# Input.net
KiCad netlist of a schematic drawn in Altium Designer
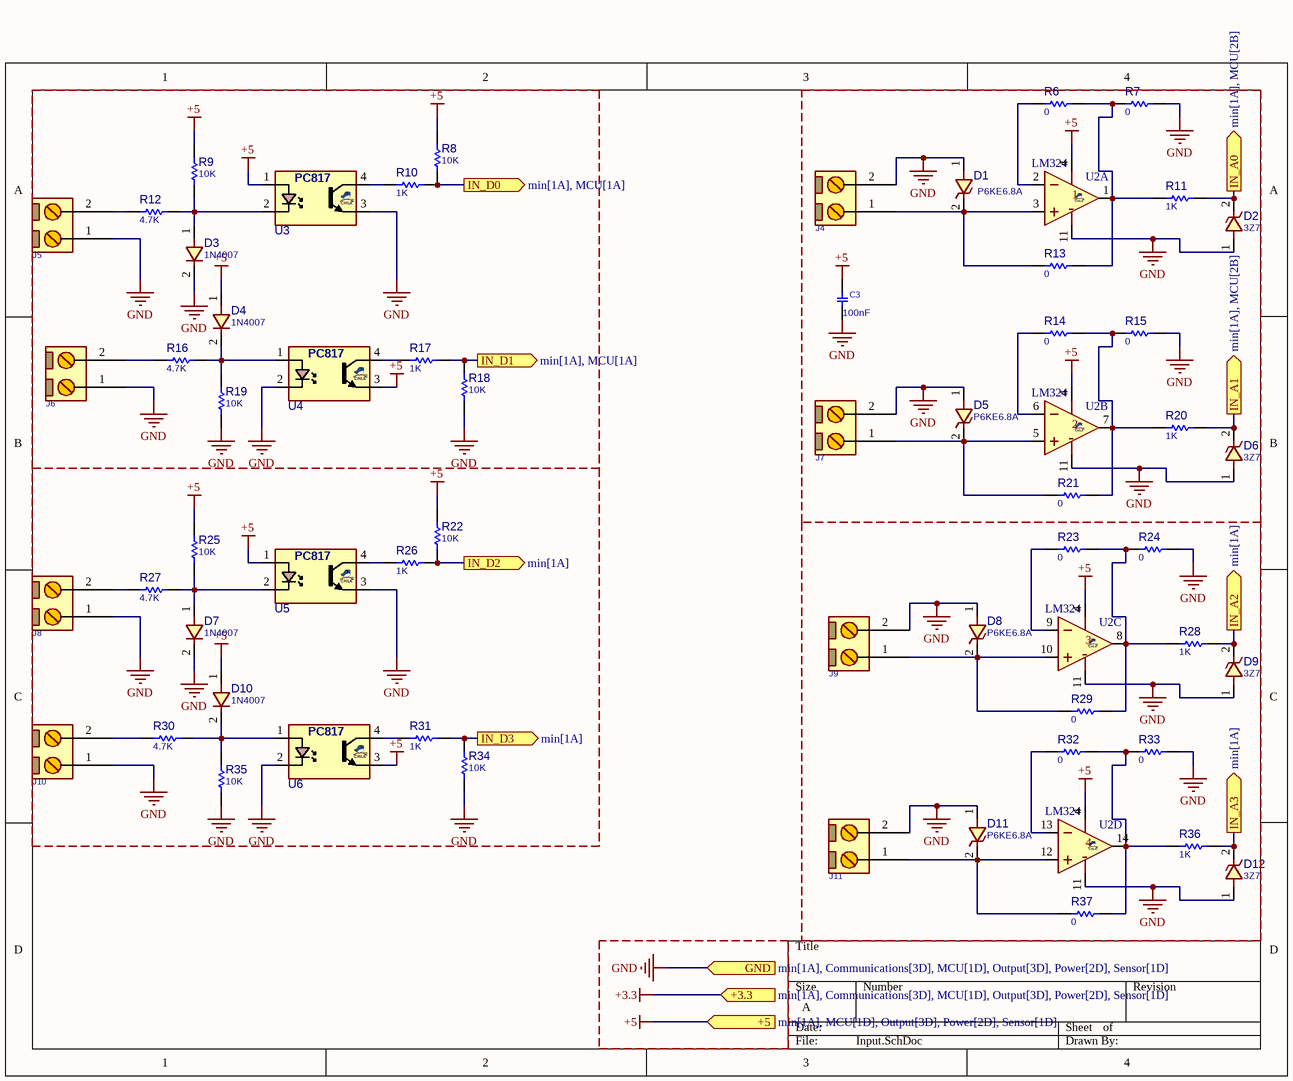
[diagram p0: Input.SchDoc]

(export (version "E")
  (design (tool "Eeschema 10.0.6"))
  (components
    (comp (ref "C3")
      (value "100nF")
      (footprint "C1206")
      (description "CAP, MLCC")
      (fields (field (name "MANF_P#") "MANF_PART#") (field (name "MANF") "Murata"))
      (libsource (lib "passive_smd") (part "CAP_SMD_MLCC"))
    )
    (comp (ref "D1")
      (value "P6KE6.8A")
      (footprint "D_AX04_DO41")
      (description "DIODE, ZENER, 0.2W, 15V")
      (fields (field (name "MANF") "Diodes") (field (name "MANF_P#") "ZENER15V"))
      (libsource (lib "diode") (part "DIODE_THD_ZENER"))
    )
    (comp (ref "D2")
      (value "3Z7")
      (footprint "D_AX04_DO41")
      (description "DIODE, ZENER, 0.2W, 15V")
      (fields (field (name "MANF") "Diodes") (field (name "MANF_P#") "ZENER15V"))
      (libsource (lib "diode") (part "DIODE_THD_ZENER"))
    )
    (comp (ref "D3")
      (value "1N4007")
      (footprint "D_AX04_DO41")
      (description "DIODE, GENERAL PURPOSE, 1000V/1A")
      (fields (field (name "MANF") "Diodes"))
      (libsource (lib "diode") (part "DIODE_THD_1N4007"))
    )
    (comp (ref "D4")
      (value "1N4007")
      (footprint "D_AX04_DO41")
      (description "DIODE, GENERAL PURPOSE, 1000V/1A")
      (fields (field (name "MANF") "Diodes"))
      (libsource (lib "diode") (part "DIODE_THD_1N4007"))
    )
    (comp (ref "D5")
      (value "P6KE6.8A")
      (footprint "D_AX04_DO41")
      (description "DIODE, ZENER, 0.2W, 15V")
      (fields (field (name "MANF") "Diodes") (field (name "MANF_P#") "ZENER15V"))
      (libsource (lib "diode") (part "DIODE_THD_ZENER"))
    )
    (comp (ref "D6")
      (value "3Z7")
      (footprint "D_AX04_DO41")
      (description "DIODE, ZENER, 0.2W, 15V")
      (fields (field (name "MANF") "Diodes") (field (name "MANF_P#") "ZENER15V"))
      (libsource (lib "diode") (part "DIODE_THD_ZENER"))
    )
    (comp (ref "D7")
      (value "1N4007")
      (footprint "D_AX04_DO41")
      (description "DIODE, GENERAL PURPOSE, 1000V/1A")
      (fields (field (name "MANF") "Diodes"))
      (libsource (lib "diode") (part "DIODE_THD_1N4007"))
    )
    (comp (ref "D8")
      (value "P6KE6.8A")
      (footprint "D_AX04_DO41")
      (description "DIODE, ZENER, 0.2W, 15V")
      (fields (field (name "MANF") "Diodes") (field (name "MANF_P#") "ZENER15V"))
      (libsource (lib "diode") (part "DIODE_THD_ZENER"))
    )
    (comp (ref "D9")
      (value "3Z7")
      (footprint "D_AX04_DO41")
      (description "DIODE, ZENER, 0.2W, 15V")
      (fields (field (name "MANF") "Diodes") (field (name "MANF_P#") "ZENER15V"))
      (libsource (lib "diode") (part "DIODE_THD_ZENER"))
    )
    (comp (ref "D10")
      (value "1N4007")
      (footprint "D_AX04_DO41")
      (description "DIODE, GENERAL PURPOSE, 1000V/1A")
      (fields (field (name "MANF") "Diodes"))
      (libsource (lib "diode") (part "DIODE_THD_1N4007"))
    )
    (comp (ref "D11")
      (value "P6KE6.8A")
      (footprint "D_AX04_DO41")
      (description "DIODE, ZENER, 0.2W, 15V")
      (fields (field (name "MANF") "Diodes") (field (name "MANF_P#") "ZENER15V"))
      (libsource (lib "diode") (part "DIODE_THD_ZENER"))
    )
    (comp (ref "D12")
      (value "3Z7")
      (footprint "D_AX04_DO41")
      (description "DIODE, ZENER, 0.2W, 15V")
      (fields (field (name "MANF") "Diodes") (field (name "MANF_P#") "ZENER15V"))
      (libsource (lib "diode") (part "DIODE_THD_ZENER"))
    )
    (comp (ref "J4")
      (value "CONN_GMSTB2")
      (footprint "GMSTB762_2")
      (description "CONN, PHOENIX GMSTB, 7.62mm pitch")
      (fields (field (name "MANF_P#") "GMSTB 2,5/2-G-7,62"))
      (libsource (lib "conn_terminalB") (part "CONN_GMSTB762_2"))
    )
    (comp (ref "J5")
      (value "CONN_GMSTB2")
      (footprint "GMSTB762_2")
      (description "CONN, PHOENIX GMSTB, 7.62mm pitch")
      (fields (field (name "MANF_P#") "GMSTB 2,5/2-G-7,62"))
      (libsource (lib "conn_terminalB") (part "CONN_GMSTB762_2"))
    )
    (comp (ref "J6")
      (value "CONN_GMSTB2")
      (footprint "GMSTB762_2")
      (description "CONN, PHOENIX GMSTB, 7.62mm pitch")
      (fields (field (name "MANF_P#") "GMSTB 2,5/2-G-7,62"))
      (libsource (lib "conn_terminalB") (part "CONN_GMSTB762_2"))
    )
    (comp (ref "J7")
      (value "CONN_GMSTB2")
      (footprint "GMSTB762_2")
      (description "CONN, PHOENIX GMSTB, 7.62mm pitch")
      (fields (field (name "MANF_P#") "GMSTB 2,5/2-G-7,62"))
      (libsource (lib "conn_terminalB") (part "CONN_GMSTB762_2"))
    )
    (comp (ref "J8")
      (value "CONN_GMSTB2")
      (footprint "GMSTB762_2")
      (description "CONN, PHOENIX GMSTB, 7.62mm pitch")
      (fields (field (name "MANF_P#") "GMSTB 2,5/2-G-7,62"))
      (libsource (lib "conn_terminalB") (part "CONN_GMSTB762_2"))
    )
    (comp (ref "J9")
      (value "CONN_GMSTB2")
      (footprint "GMSTB762_2")
      (description "CONN, PHOENIX GMSTB, 7.62mm pitch")
      (fields (field (name "MANF_P#") "GMSTB 2,5/2-G-7,62"))
      (libsource (lib "conn_terminalB") (part "CONN_GMSTB762_2"))
    )
    (comp (ref "J10")
      (value "CONN_GMSTB2")
      (footprint "GMSTB762_2")
      (description "CONN, PHOENIX GMSTB, 7.62mm pitch")
      (fields (field (name "MANF_P#") "GMSTB 2,5/2-G-7,62"))
      (libsource (lib "conn_terminalB") (part "CONN_GMSTB762_2"))
    )
    (comp (ref "J11")
      (value "CONN_GMSTB2")
      (footprint "GMSTB762_2")
      (description "CONN, PHOENIX GMSTB, 7.62mm pitch")
      (fields (field (name "MANF_P#") "GMSTB 2,5/2-G-7,62"))
      (libsource (lib "conn_terminalB") (part "CONN_GMSTB762_2"))
    )
    (comp (ref "R6")
      (value "0")
      (footprint "R1206")
      (description "RESISTOR, SMD")
      (libsource (lib "passive_smd") (part "RES_SMD"))
    )
    (comp (ref "R7")
      (value "0")
      (footprint "R1206")
      (description "RESISTOR, SMD")
      (libsource (lib "passive_smd") (part "RES_SMD"))
    )
    (comp (ref "R8")
      (value "10K")
      (footprint "R1206")
      (description "RESISTOR, SMD")
      (libsource (lib "passive_smd") (part "RES_SMD"))
    )
    (comp (ref "R9")
      (value "10K")
      (footprint "R1206")
      (description "RESISTOR, SMD")
      (libsource (lib "passive_smd") (part "RES_SMD"))
    )
    (comp (ref "R10")
      (value "1K")
      (footprint "R1206")
      (description "RESISTOR, SMD")
      (libsource (lib "passive_smd") (part "RES_SMD"))
    )
    (comp (ref "R11")
      (value "1K")
      (footprint "R1206")
      (description "RESISTOR, SMD")
      (libsource (lib "passive_smd") (part "RES_SMD"))
    )
    (comp (ref "R12")
      (value "4.7K")
      (footprint "R1206")
      (description "RESISTOR, SMD")
      (libsource (lib "passive_smd") (part "RES_SMD"))
    )
    (comp (ref "R13")
      (value "0")
      (footprint "R1206")
      (description "RESISTOR, SMD")
      (libsource (lib "passive_smd") (part "RES_SMD"))
    )
    (comp (ref "R14")
      (value "0")
      (footprint "R1206")
      (description "RESISTOR, SMD")
      (libsource (lib "passive_smd") (part "RES_SMD"))
    )
    (comp (ref "R15")
      (value "0")
      (footprint "R1206")
      (description "RESISTOR, SMD")
      (libsource (lib "passive_smd") (part "RES_SMD"))
    )
    (comp (ref "R16")
      (value "4.7K")
      (footprint "R1206")
      (description "RESISTOR, SMD")
      (libsource (lib "passive_smd") (part "RES_SMD"))
    )
    (comp (ref "R17")
      (value "1K")
      (footprint "R1206")
      (description "RESISTOR, SMD")
      (libsource (lib "passive_smd") (part "RES_SMD"))
    )
    (comp (ref "R18")
      (value "10K")
      (footprint "R1206")
      (description "RESISTOR, SMD")
      (libsource (lib "passive_smd") (part "RES_SMD"))
    )
    (comp (ref "R19")
      (value "10K")
      (footprint "R1206")
      (description "RESISTOR, SMD")
      (libsource (lib "passive_smd") (part "RES_SMD"))
    )
    (comp (ref "R20")
      (value "1K")
      (footprint "R1206")
      (description "RESISTOR, SMD")
      (libsource (lib "passive_smd") (part "RES_SMD"))
    )
    (comp (ref "R21")
      (value "0")
      (footprint "R1206")
      (description "RESISTOR, SMD")
      (libsource (lib "passive_smd") (part "RES_SMD"))
    )
    (comp (ref "R22")
      (value "10K")
      (footprint "R1206")
      (description "RESISTOR, SMD")
      (libsource (lib "passive_smd") (part "RES_SMD"))
    )
    (comp (ref "R23")
      (value "0")
      (footprint "R1206")
      (description "RESISTOR, SMD")
      (libsource (lib "passive_smd") (part "RES_SMD"))
    )
    (comp (ref "R24")
      (value "0")
      (footprint "R1206")
      (description "RESISTOR, SMD")
      (libsource (lib "passive_smd") (part "RES_SMD"))
    )
    (comp (ref "R25")
      (value "10K")
      (footprint "R1206")
      (description "RESISTOR, SMD")
      (libsource (lib "passive_smd") (part "RES_SMD"))
    )
    (comp (ref "R26")
      (value "1K")
      (footprint "R1206")
      (description "RESISTOR, SMD")
      (libsource (lib "passive_smd") (part "RES_SMD"))
    )
    (comp (ref "R27")
      (value "4.7K")
      (footprint "R1206")
      (description "RESISTOR, SMD")
      (libsource (lib "passive_smd") (part "RES_SMD"))
    )
    (comp (ref "R28")
      (value "1K")
      (footprint "R1206")
      (description "RESISTOR, SMD")
      (libsource (lib "passive_smd") (part "RES_SMD"))
    )
    (comp (ref "R29")
      (value "0")
      (footprint "R1206")
      (description "RESISTOR, SMD")
      (libsource (lib "passive_smd") (part "RES_SMD"))
    )
    (comp (ref "R30")
      (value "4.7K")
      (footprint "R1206")
      (description "RESISTOR, SMD")
      (libsource (lib "passive_smd") (part "RES_SMD"))
    )
    (comp (ref "R31")
      (value "1K")
      (footprint "R1206")
      (description "RESISTOR, SMD")
      (libsource (lib "passive_smd") (part "RES_SMD"))
    )
    (comp (ref "R32")
      (value "0")
      (footprint "R1206")
      (description "RESISTOR, SMD")
      (libsource (lib "passive_smd") (part "RES_SMD"))
    )
    (comp (ref "R33")
      (value "0")
      (footprint "R1206")
      (description "RESISTOR, SMD")
      (libsource (lib "passive_smd") (part "RES_SMD"))
    )
    (comp (ref "R34")
      (value "10K")
      (footprint "R1206")
      (description "RESISTOR, SMD")
      (libsource (lib "passive_smd") (part "RES_SMD"))
    )
    (comp (ref "R35")
      (value "10K")
      (footprint "R1206")
      (description "RESISTOR, SMD")
      (libsource (lib "passive_smd") (part "RES_SMD"))
    )
    (comp (ref "R36")
      (value "1K")
      (footprint "R1206")
      (description "RESISTOR, SMD")
      (libsource (lib "passive_smd") (part "RES_SMD"))
    )
    (comp (ref "R37")
      (value "0")
      (footprint "R1206")
      (description "RESISTOR, SMD")
      (libsource (lib "passive_smd") (part "RES_SMD"))
    )
    (comp (ref "U2")
      (value "LM324")
      (footprint "DIP_14")
      (description "AMP, Quad, Single-Supply")
      (fields (field (name "MANF") "ON, Texas Instruments, ST") (field (name "MANF_P#") "LM324AN"))
      (libsource (lib "amp") (part "LM324_DIP14"))
    )
    (comp (ref "U3")
      (value "PC817")
      (footprint "DIP_4")
      (description "OPTOCOUPLER, TRANSISTOR, 4PIN")
      (fields (field (name "MANF") "SHARP"))
      (libsource (lib "optocoupler") (part "OPTC_TR4P_PC817"))
    )
    (comp (ref "U4")
      (value "PC817")
      (footprint "DIP_4")
      (description "OPTOCOUPLER, TRANSISTOR, 4PIN")
      (fields (field (name "MANF") "SHARP"))
      (libsource (lib "optocoupler") (part "OPTC_TR4P_PC817"))
    )
    (comp (ref "U5")
      (value "PC817")
      (footprint "DIP_4")
      (description "OPTOCOUPLER, TRANSISTOR, 4PIN")
      (fields (field (name "MANF") "SHARP"))
      (libsource (lib "optocoupler") (part "OPTC_TR4P_PC817"))
    )
    (comp (ref "U6")
      (value "PC817")
      (footprint "DIP_4")
      (description "OPTOCOUPLER, TRANSISTOR, 4PIN")
      (fields (field (name "MANF") "SHARP"))
      (libsource (lib "optocoupler") (part "OPTC_TR4P_PC817"))
    )
  )
  (nets
    (net (code "2") (name "+5") (class "Default")
      (node (ref "C3") (pin "1") (pinfunction "1_1") (pintype "passive"))
      (node (ref "D10") (pin "1") (pinfunction "1_1") (pintype "passive"))
      (node (ref "D4") (pin "1") (pinfunction "1_1") (pintype "passive"))
      (node (ref "R22") (pin "2") (pinfunction "2_2") (pintype "passive"))
      (node (ref "R25") (pin "2") (pinfunction "2_2") (pintype "passive"))
      (node (ref "R8") (pin "2") (pinfunction "2_2") (pintype "passive"))
      (node (ref "R9") (pin "2") (pinfunction "2_2") (pintype "passive"))
      (node (ref "U2") (pin "4") (pinfunction "V+_4") (pintype "passive"))
      (node (ref "U3") (pin "1") (pinfunction "A_1") (pintype "passive"))
      (node (ref "U4") (pin "3") (pinfunction "E_3") (pintype "passive"))
      (node (ref "U5") (pin "1") (pinfunction "A_1") (pintype "passive"))
      (node (ref "U6") (pin "3") (pinfunction "E_3") (pintype "passive"))
    )
    (net (code "3") (name "/IN_A0") (class "Default")
      (node (ref "D2") (pin "2") (pinfunction "2_2") (pintype "passive"))
      (node (ref "R11") (pin "2") (pinfunction "2_2") (pintype "passive"))
    )
    (net (code "4") (name "/IN_A1") (class "Default")
      (node (ref "D6") (pin "2") (pinfunction "2_2") (pintype "passive"))
      (node (ref "R20") (pin "2") (pinfunction "2_2") (pintype "passive"))
    )
    (net (code "5") (name "/IN_A2") (class "Default")
      (node (ref "D9") (pin "2") (pinfunction "2_2") (pintype "passive"))
      (node (ref "R28") (pin "2") (pinfunction "2_2") (pintype "passive"))
    )
    (net (code "6") (name "/IN_A3") (class "Default")
      (node (ref "D12") (pin "2") (pinfunction "2_2") (pintype "passive"))
      (node (ref "R36") (pin "2") (pinfunction "2_2") (pintype "passive"))
    )
    (net (code "7") (name "/IN_D0") (class "Default")
      (node (ref "R10") (pin "2") (pinfunction "2_2") (pintype "passive"))
      (node (ref "R8") (pin "1") (pinfunction "1_1") (pintype "passive"))
    )
    (net (code "8") (name "/IN_D1") (class "Default")
      (node (ref "R17") (pin "2") (pinfunction "2_2") (pintype "passive"))
      (node (ref "R18") (pin "2") (pinfunction "2_2") (pintype "passive"))
    )
    (net (code "9") (name "/IN_D2") (class "Default")
      (node (ref "R22") (pin "1") (pinfunction "1_1") (pintype "passive"))
      (node (ref "R26") (pin "2") (pinfunction "2_2") (pintype "passive"))
    )
    (net (code "10") (name "/IN_D3") (class "Default")
      (node (ref "R31") (pin "2") (pinfunction "2_2") (pintype "passive"))
      (node (ref "R34") (pin "2") (pinfunction "2_2") (pintype "passive"))
    )
    (net (code "11") (name "GND") (class "Default")
      (node (ref "C3") (pin "2") (pinfunction "2_2") (pintype "passive"))
      (node (ref "D1") (pin "1") (pinfunction "1_1") (pintype "passive"))
      (node (ref "D11") (pin "1") (pinfunction "1_1") (pintype "passive"))
      (node (ref "D12") (pin "1") (pinfunction "1_1") (pintype "passive"))
      (node (ref "D2") (pin "1") (pinfunction "1_1") (pintype "passive"))
      (node (ref "D3") (pin "2") (pinfunction "2_2") (pintype "passive"))
      (node (ref "D5") (pin "1") (pinfunction "1_1") (pintype "passive"))
      (node (ref "D6") (pin "1") (pinfunction "1_1") (pintype "passive"))
      (node (ref "D7") (pin "2") (pinfunction "2_2") (pintype "passive"))
      (node (ref "D8") (pin "1") (pinfunction "1_1") (pintype "passive"))
      (node (ref "D9") (pin "1") (pinfunction "1_1") (pintype "passive"))
      (node (ref "J10") (pin "1") (pinfunction "1_1") (pintype "passive"))
      (node (ref "J11") (pin "2") (pinfunction "2_2") (pintype "passive"))
      (node (ref "J4") (pin "2") (pinfunction "2_2") (pintype "passive"))
      (node (ref "J5") (pin "1") (pinfunction "1_1") (pintype "passive"))
      (node (ref "J6") (pin "1") (pinfunction "1_1") (pintype "passive"))
      (node (ref "J7") (pin "2") (pinfunction "2_2") (pintype "passive"))
      (node (ref "J8") (pin "1") (pinfunction "1_1") (pintype "passive"))
      (node (ref "J9") (pin "2") (pinfunction "2_2") (pintype "passive"))
      (node (ref "R15") (pin "1") (pinfunction "1_1") (pintype "passive"))
      (node (ref "R18") (pin "1") (pinfunction "1_1") (pintype "passive"))
      (node (ref "R19") (pin "1") (pinfunction "1_1") (pintype "passive"))
      (node (ref "R24") (pin "1") (pinfunction "1_1") (pintype "passive"))
      (node (ref "R33") (pin "1") (pinfunction "1_1") (pintype "passive"))
      (node (ref "R34") (pin "1") (pinfunction "1_1") (pintype "passive"))
      (node (ref "R35") (pin "1") (pinfunction "1_1") (pintype "passive"))
      (node (ref "R7") (pin "1") (pinfunction "1_1") (pintype "passive"))
      (node (ref "U2") (pin "11") (pinfunction "V-_11") (pintype "passive"))
      (node (ref "U3") (pin "3") (pinfunction "E_3") (pintype "passive"))
      (node (ref "U4") (pin "2") (pinfunction "K_2") (pintype "passive"))
      (node (ref "U5") (pin "3") (pinfunction "E_3") (pintype "passive"))
      (node (ref "U6") (pin "2") (pinfunction "K_2") (pintype "passive"))
    )
    (net (code "12") (name "Net-(J5-Pad2)") (class "Default")
      (node (ref "J5") (pin "2") (pinfunction "2_2") (pintype "passive"))
      (node (ref "R12") (pin "2") (pinfunction "2_2") (pintype "passive"))
    )
    (net (code "13") (name "Net-(J6-Pad2)") (class "Default")
      (node (ref "J6") (pin "2") (pinfunction "2_2") (pintype "passive"))
      (node (ref "R16") (pin "2") (pinfunction "2_2") (pintype "passive"))
    )
    (net (code "14") (name "Net-(J8-Pad2)") (class "Default")
      (node (ref "J8") (pin "2") (pinfunction "2_2") (pintype "passive"))
      (node (ref "R27") (pin "2") (pinfunction "2_2") (pintype "passive"))
    )
    (net (code "15") (name "Net-(J10-Pad2)") (class "Default")
      (node (ref "J10") (pin "2") (pinfunction "2_2") (pintype "passive"))
      (node (ref "R30") (pin "2") (pinfunction "2_2") (pintype "passive"))
    )
    (net (code "16") (name "Net-(U2A-IN+)") (class "Default")
      (node (ref "D1") (pin "2") (pinfunction "2_2") (pintype "passive"))
      (node (ref "J4") (pin "1") (pinfunction "1_1") (pintype "passive"))
      (node (ref "R13") (pin "2") (pinfunction "2_2") (pintype "passive"))
      (node (ref "U2") (pin "3") (pinfunction "IN+_3") (pintype "passive"))
    )
    (net (code "17") (name "Net-(U2A-IN-)") (class "Default")
      (node (ref "R6") (pin "2") (pinfunction "2_2") (pintype "passive"))
      (node (ref "U2") (pin "2") (pinfunction "IN-_2") (pintype "passive"))
    )
    (net (code "18") (name "Net-(U2A-OUT)") (class "Default")
      (node (ref "R11") (pin "1") (pinfunction "1_1") (pintype "passive"))
      (node (ref "R13") (pin "1") (pinfunction "1_1") (pintype "passive"))
      (node (ref "R6") (pin "1") (pinfunction "1_1") (pintype "passive"))
      (node (ref "R7") (pin "2") (pinfunction "2_2") (pintype "passive"))
      (node (ref "U2") (pin "1") (pinfunction "OUT_1") (pintype "passive"))
    )
    (net (code "19") (name "Net-(U2B-IN+)") (class "Default")
      (node (ref "D5") (pin "2") (pinfunction "2_2") (pintype "passive"))
      (node (ref "J7") (pin "1") (pinfunction "1_1") (pintype "passive"))
      (node (ref "R21") (pin "2") (pinfunction "2_2") (pintype "passive"))
      (node (ref "U2") (pin "5") (pinfunction "IN+_5") (pintype "passive"))
    )
    (net (code "20") (name "Net-(U2B-IN-)") (class "Default")
      (node (ref "R14") (pin "2") (pinfunction "2_2") (pintype "passive"))
      (node (ref "U2") (pin "6") (pinfunction "IN-_6") (pintype "passive"))
    )
    (net (code "21") (name "Net-(U2B-OUT)") (class "Default")
      (node (ref "R14") (pin "1") (pinfunction "1_1") (pintype "passive"))
      (node (ref "R15") (pin "2") (pinfunction "2_2") (pintype "passive"))
      (node (ref "R20") (pin "1") (pinfunction "1_1") (pintype "passive"))
      (node (ref "R21") (pin "1") (pinfunction "1_1") (pintype "passive"))
      (node (ref "U2") (pin "7") (pinfunction "OUT_7") (pintype "passive"))
    )
    (net (code "22") (name "Net-(U2C-IN+)") (class "Default")
      (node (ref "D8") (pin "2") (pinfunction "2_2") (pintype "passive"))
      (node (ref "J9") (pin "1") (pinfunction "1_1") (pintype "passive"))
      (node (ref "R29") (pin "2") (pinfunction "2_2") (pintype "passive"))
      (node (ref "U2") (pin "10") (pinfunction "IN+_10") (pintype "passive"))
    )
    (net (code "23") (name "Net-(U2C-IN-)") (class "Default")
      (node (ref "R23") (pin "2") (pinfunction "2_2") (pintype "passive"))
      (node (ref "U2") (pin "9") (pinfunction "IN-_9") (pintype "passive"))
    )
    (net (code "24") (name "Net-(U2C-OUT)") (class "Default")
      (node (ref "R23") (pin "1") (pinfunction "1_1") (pintype "passive"))
      (node (ref "R24") (pin "2") (pinfunction "2_2") (pintype "passive"))
      (node (ref "R28") (pin "1") (pinfunction "1_1") (pintype "passive"))
      (node (ref "R29") (pin "1") (pinfunction "1_1") (pintype "passive"))
      (node (ref "U2") (pin "8") (pinfunction "OUT_8") (pintype "passive"))
    )
    (net (code "25") (name "Net-(U2D-IN+)") (class "Default")
      (node (ref "D11") (pin "2") (pinfunction "2_2") (pintype "passive"))
      (node (ref "J11") (pin "1") (pinfunction "1_1") (pintype "passive"))
      (node (ref "R37") (pin "2") (pinfunction "2_2") (pintype "passive"))
      (node (ref "U2") (pin "12") (pinfunction "IN+_12") (pintype "passive"))
    )
    (net (code "26") (name "Net-(U2D-IN-)") (class "Default")
      (node (ref "R32") (pin "2") (pinfunction "2_2") (pintype "passive"))
      (node (ref "U2") (pin "13") (pinfunction "IN-_13") (pintype "passive"))
    )
    (net (code "27") (name "Net-(U2D-OUT)") (class "Default")
      (node (ref "R32") (pin "1") (pinfunction "1_1") (pintype "passive"))
      (node (ref "R33") (pin "2") (pinfunction "2_2") (pintype "passive"))
      (node (ref "R36") (pin "1") (pinfunction "1_1") (pintype "passive"))
      (node (ref "R37") (pin "1") (pinfunction "1_1") (pintype "passive"))
      (node (ref "U2") (pin "14") (pinfunction "OUT_14") (pintype "passive"))
    )
    (net (code "28") (name "Net-(U3-C)") (class "Default")
      (node (ref "R10") (pin "1") (pinfunction "1_1") (pintype "passive"))
      (node (ref "U3") (pin "4") (pinfunction "C_4") (pintype "passive"))
    )
    (net (code "29") (name "Net-(U3-K)") (class "Default")
      (node (ref "D3") (pin "1") (pinfunction "1_1") (pintype "passive"))
      (node (ref "R12") (pin "1") (pinfunction "1_1") (pintype "passive"))
      (node (ref "R9") (pin "1") (pinfunction "1_1") (pintype "passive"))
      (node (ref "U3") (pin "2") (pinfunction "K_2") (pintype "passive"))
    )
    (net (code "30") (name "Net-(U4-A)") (class "Default")
      (node (ref "D4") (pin "2") (pinfunction "2_2") (pintype "passive"))
      (node (ref "R16") (pin "1") (pinfunction "1_1") (pintype "passive"))
      (node (ref "R19") (pin "2") (pinfunction "2_2") (pintype "passive"))
      (node (ref "U4") (pin "1") (pinfunction "A_1") (pintype "passive"))
    )
    (net (code "31") (name "Net-(U4-C)") (class "Default")
      (node (ref "R17") (pin "1") (pinfunction "1_1") (pintype "passive"))
      (node (ref "U4") (pin "4") (pinfunction "C_4") (pintype "passive"))
    )
    (net (code "32") (name "Net-(U5-C)") (class "Default")
      (node (ref "R26") (pin "1") (pinfunction "1_1") (pintype "passive"))
      (node (ref "U5") (pin "4") (pinfunction "C_4") (pintype "passive"))
    )
    (net (code "33") (name "Net-(U5-K)") (class "Default")
      (node (ref "D7") (pin "1") (pinfunction "1_1") (pintype "passive"))
      (node (ref "R25") (pin "1") (pinfunction "1_1") (pintype "passive"))
      (node (ref "R27") (pin "1") (pinfunction "1_1") (pintype "passive"))
      (node (ref "U5") (pin "2") (pinfunction "K_2") (pintype "passive"))
    )
    (net (code "34") (name "Net-(U6-A)") (class "Default")
      (node (ref "D10") (pin "2") (pinfunction "2_2") (pintype "passive"))
      (node (ref "R30") (pin "1") (pinfunction "1_1") (pintype "passive"))
      (node (ref "R35") (pin "2") (pinfunction "2_2") (pintype "passive"))
      (node (ref "U6") (pin "1") (pinfunction "A_1") (pintype "passive"))
    )
    (net (code "35") (name "Net-(U6-C)") (class "Default")
      (node (ref "R31") (pin "1") (pinfunction "1_1") (pintype "passive"))
      (node (ref "U6") (pin "4") (pinfunction "C_4") (pintype "passive"))
    )
  )
)
